# TagConnectProgrammer.net
KiCad netlist of a schematic drawn in Altium Designer
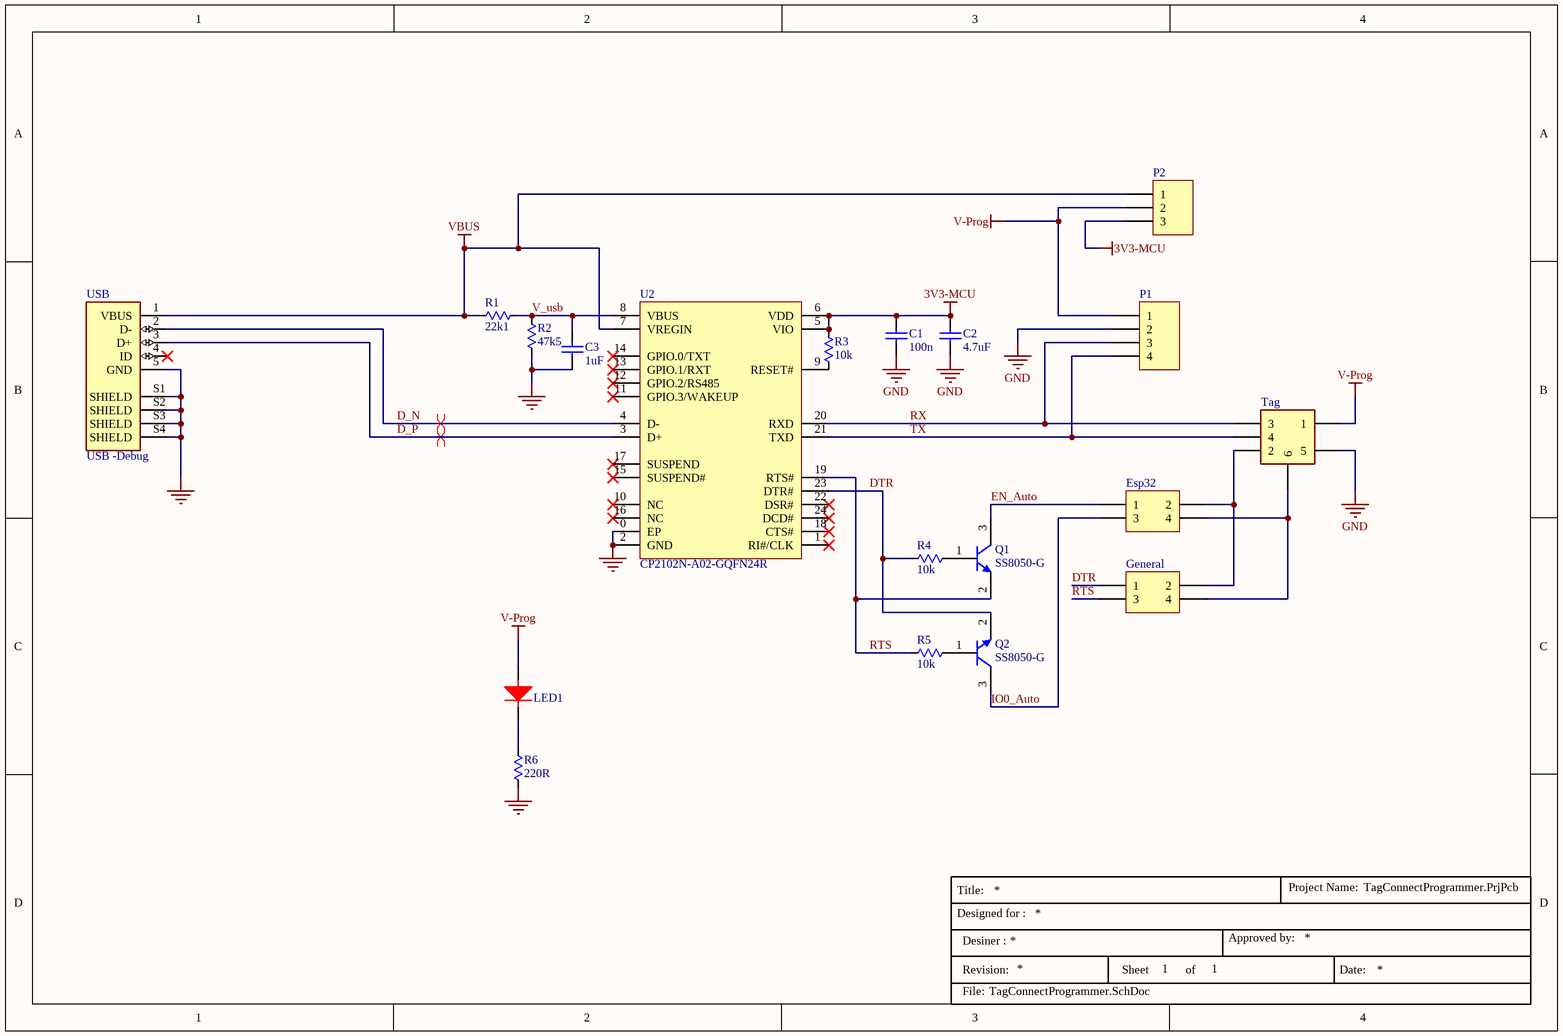
[diagram p0: TagConnectProgrammer.SchDoc]

(export (version "E")
  (design (tool "Eeschema 10.0.6"))
  (components
    (comp (ref "C1")
      (value "100n")
      (footprint "0603C")
      (description "Multilayer Ceramic Capacitors MLCC - SMD/SMT 16V 0.1uF X7R 0603 10%")
      (libsource (lib "Aves") (part "100n"))
    )
    (comp (ref "C2")
      (value "4.7uF")
      (footprint "0603C")
      (description "Multilayer Ceramic Capacitors MLCC - SMD/SMT 4.7uF+/-10% 10V X5R 1608")
      (libsource (lib "Aves") (part "4.7uF"))
    )
    (comp (ref "C3")
      (value "1uF")
      (footprint "0603C")
      (description "Multilayer Ceramic Capacitors MLCC - SMD/SMT 1uF+/-10% 10V X5R 1608")
      (libsource (lib "Aves") (part "1uF"))
    )
    (comp (ref "Esp32")
      (value "Header 2X2")
      (footprint "HDR2X2")
      (description "Header, 4-Pin, Dual row 100 mil")
      (fields (field (name "PUBLISHER") "Altium Limited"))
      (libsource (lib "Miscellaneous Connectors") (part "Header 2X2"))
    )
    (comp (ref "General")
      (value "Header 2X2")
      (footprint "HDR2X2")
      (description "Header, 4-Pin, Dual row 100 mil")
      (fields (field (name "PUBLISHER") "Altium Limited"))
      (libsource (lib "Miscellaneous Connectors") (part "Header 2X2"))
    )
    (comp (ref "LED1")
      (value "150060VS55040")
      (footprint "Würth_Elektronik_0_MFG")
      (description "Standard LEDs - SMD SMD 0603 RED")
      (libsource (lib "MikroFirm") (part "LED R"))
    )
    (comp (ref "P1")
      (value "Header 4")
      (footprint "HDR1X4")
      (description "Header, 4-Pin,One row 100 mil")
      (fields (field (name "PUBLISHER") "Altium Limited"))
      (libsource (lib "Miscellaneous Connectors") (part "Header 4"))
    )
    (comp (ref "P2")
      (value "Header 3")
      (footprint "HDR1X3")
      (description "Header, 3-Pin,One row 100 mil")
      (fields (field (name "PUBLISHER") "Altium Limited"))
      (libsource (lib "Miscellaneous Connectors") (part "Header 3"))
    )
    (comp (ref "Q1")
      (value "SS8050-G")
      (footprint "SOT95P240X115-3N")
      (description "NPN TRANSISTOR 1.5A 40V SOT-23 R")
      (libsource (lib "Aves") (part "SS8050-G"))
    )
    (comp (ref "Q2")
      (value "SS8050-G")
      (footprint "SOT95P240X115-3N")
      (description "NPN TRANSISTOR 1.5A 40V SOT-23 R")
      (libsource (lib "Aves") (part "SS8050-G"))
    )
    (comp (ref "R1")
      (value "22k1")
      (footprint "0603R")
      (description "Thick Film Resistors - SMD 0603 22Kohms 1% AEC-Q200")
      (libsource (lib "Aves") (part "22k1"))
    )
    (comp (ref "R2")
      (value "47k5")
      (footprint "0603R")
      (description "Thin Film Resistors - SMD 1/8W 47.5K ohm 1% 50ppm")
      (libsource (lib "Aves") (part "47k5"))
    )
    (comp (ref "R3")
      (value "10k")
      (footprint "0603R")
      (description "Thick Film Resistors - SMD 0603 10Kohms 1% AEC-Q200")
      (libsource (lib "Aves") (part "10k"))
    )
    (comp (ref "R4")
      (value "10k")
      (footprint "0603R")
      (description "Thick Film Resistors - SMD 0603 10Kohms 1% AEC-Q200")
      (libsource (lib "Aves") (part "10k"))
    )
    (comp (ref "R5")
      (value "10k")
      (footprint "0603R")
      (description "Thick Film Resistors - SMD 0603 10Kohms 1% AEC-Q200")
      (libsource (lib "Aves") (part "10k"))
    )
    (comp (ref "R6")
      (value "220R")
      (footprint "0603R")
      (description "Thick Film Resistors - SMD 220 Ohms 100-200 mW 0603 1%")
      (libsource (lib "MikroFirm") (part "220R"))
    )
    (comp (ref "Tag")
      (value "Header 3X2H BOX")
      (footprint "SHDRRA6W64P254X254_2X3_1528X885X910P")
      (description "Headers & Wire Housings WR-BHD 2.54mm Male 6P Angl Gold BoX Hdr")
      (fields
        (field (name "MANUFACTURER_PART_NUMBER") "61200621721")
        (field (name "MOUSER PART NUMBER") "710-61200621721")
      )
      (libsource (lib "MikroFirm") (part "Header 3X2H BOX"))
    )
    (comp (ref "U2")
      (value "CP2102N-A02-GQFN24R")
      (footprint "QFN50P400X400X80-25N")
      (description "IC USB TO UART BRIDGE QFN24")
      (libsource (lib "Aves") (part "CP2102N-A02-GQFN20R"))
    )
    (comp (ref "USB")
      (value "USB -Debug")
      (footprint "MOLEX_47642-0001")
      (description "USB - micro B Receptacle Connector 5 Position Board Edge, Cutout; Surface Mount, Right Angle")
      (libsource (lib "Aves") (part "USB - micro B"))
    )
  )
  (nets
    (net (code "1") (name "/DTR") (class "Default")
      (node (ref "General") (pin "1") (pinfunction "1_1") (pintype "passive"))
      (node (ref "Q2") (pin "2") (pinfunction "E_2") (pintype "passive"))
      (node (ref "R4") (pin "2") (pinfunction "2_2") (pintype "passive"))
      (node (ref "U2") (pin "23") (pinfunction "DTR#_23") (pintype "passive"))
    )
    (net (code "2") (name "/D_N") (class "Default")
      (node (ref "U2") (pin "4") (pinfunction "D-_4") (pintype "passive"))
      (node (ref "USB") (pin "2") (pinfunction "D-_2") (pintype "bidirectional"))
    )
    (net (code "3") (name "/D_P") (class "Default")
      (node (ref "U2") (pin "3") (pinfunction "D+_3") (pintype "passive"))
      (node (ref "USB") (pin "3") (pinfunction "D+_3") (pintype "bidirectional"))
    )
    (net (code "4") (name "/EN_Auto") (class "Default")
      (node (ref "Esp32") (pin "1") (pinfunction "1_1") (pintype "passive"))
      (node (ref "Q1") (pin "3") (pinfunction "C_3") (pintype "passive"))
    )
    (net (code "5") (name "/IO0_Auto") (class "Default")
      (node (ref "Esp32") (pin "3") (pinfunction "3_3") (pintype "passive"))
      (node (ref "Q2") (pin "3") (pinfunction "C_3") (pintype "passive"))
    )
    (net (code "6") (name "/RTS") (class "Default")
      (node (ref "General") (pin "3") (pinfunction "3_3") (pintype "passive"))
      (node (ref "Q1") (pin "2") (pinfunction "E_2") (pintype "passive"))
      (node (ref "R5") (pin "2") (pinfunction "2_2") (pintype "passive"))
      (node (ref "U2") (pin "19") (pinfunction "RTS#_19") (pintype "passive"))
    )
    (net (code "7") (name "/RX") (class "Default")
      (node (ref "P1") (pin "3") (pinfunction "3_3") (pintype "passive"))
      (node (ref "Tag") (pin "3") (pinfunction "3_3") (pintype "passive"))
      (node (ref "U2") (pin "20") (pinfunction "RXD_20") (pintype "passive"))
    )
    (net (code "8") (name "/TX") (class "Default")
      (node (ref "P1") (pin "4") (pinfunction "4_4") (pintype "passive"))
      (node (ref "Tag") (pin "4") (pinfunction "4_4") (pintype "passive"))
      (node (ref "U2") (pin "21") (pinfunction "TXD_21") (pintype "passive"))
    )
    (net (code "9") (name "/V_usb") (class "Default")
      (node (ref "C3") (pin "2") (pinfunction "2_2") (pintype "passive"))
      (node (ref "R1") (pin "2") (pinfunction "2_2") (pintype "passive"))
      (node (ref "R2") (pin "2") (pinfunction "2_2") (pintype "passive"))
      (node (ref "U2") (pin "8") (pinfunction "VBUS_8") (pintype "passive"))
    )
    (net (code "10") (name "3V3-MCU") (class "Default")
      (node (ref "C1") (pin "2") (pinfunction "2_2") (pintype "passive"))
      (node (ref "C2") (pin "2") (pinfunction "2_2") (pintype "passive"))
      (node (ref "P2") (pin "3") (pinfunction "3_3") (pintype "passive"))
      (node (ref "R3") (pin "2") (pinfunction "2_2") (pintype "passive"))
      (node (ref "U2") (pin "5") (pinfunction "VIO_5") (pintype "passive"))
      (node (ref "U2") (pin "6") (pinfunction "VDD_6") (pintype "passive"))
    )
    (net (code "11") (name "GND") (class "Default")
      (node (ref "C1") (pin "1") (pinfunction "1_1") (pintype "passive"))
      (node (ref "C2") (pin "1") (pinfunction "1_1") (pintype "passive"))
      (node (ref "C3") (pin "1") (pinfunction "1_1") (pintype "passive"))
      (node (ref "P1") (pin "2") (pinfunction "2_2") (pintype "passive"))
      (node (ref "R2") (pin "1") (pinfunction "1_1") (pintype "passive"))
      (node (ref "R6") (pin "1") (pinfunction "1_1") (pintype "passive"))
      (node (ref "Tag") (pin "5") (pinfunction "5_5") (pintype "passive"))
      (node (ref "U2") (pin "0") (pinfunction "EP_0") (pintype "passive"))
      (node (ref "U2") (pin "2") (pinfunction "GND_2") (pintype "passive"))
      (node (ref "USB") (pin "5") (pinfunction "GND_5") (pintype "power_in"))
      (node (ref "USB") (pin "S1") (pinfunction "SHIELD_S1") (pintype "power_in"))
      (node (ref "USB") (pin "S2") (pinfunction "SHIELD_S2") (pintype "power_in"))
      (node (ref "USB") (pin "S3") (pinfunction "SHIELD_S3") (pintype "power_in"))
      (node (ref "USB") (pin "S4") (pinfunction "SHIELD_S4") (pintype "power_in"))
    )
    (net (code "12") (name "Net-(Esp32-Pad2)") (class "Default")
      (node (ref "Esp32") (pin "2") (pinfunction "2_2") (pintype "passive"))
      (node (ref "General") (pin "2") (pinfunction "2_2") (pintype "passive"))
      (node (ref "Tag") (pin "2") (pinfunction "2_2") (pintype "passive"))
    )
    (net (code "13") (name "Net-(Esp32-Pad4)") (class "Default")
      (node (ref "Esp32") (pin "4") (pinfunction "4_4") (pintype "passive"))
      (node (ref "General") (pin "4") (pinfunction "4_4") (pintype "passive"))
      (node (ref "Tag") (pin "6") (pinfunction "6_6") (pintype "passive"))
    )
    (net (code "14") (name "Net-(LED1--)") (class "Default")
      (node (ref "LED1") (pin "1") (pinfunction "-_1") (pintype "passive"))
      (node (ref "R6") (pin "2") (pinfunction "2_2") (pintype "passive"))
    )
    (net (code "15") (name "Net-(Q1-B)") (class "Default")
      (node (ref "Q1") (pin "1") (pinfunction "B_1") (pintype "passive"))
      (node (ref "R4") (pin "1") (pinfunction "1_1") (pintype "passive"))
    )
    (net (code "16") (name "Net-(Q2-B)") (class "Default")
      (node (ref "Q2") (pin "1") (pinfunction "B_1") (pintype "passive"))
      (node (ref "R5") (pin "1") (pinfunction "1_1") (pintype "passive"))
    )
    (net (code "17") (name "Net-(U2-RESET#)") (class "Default")
      (node (ref "R3") (pin "1") (pinfunction "1_1") (pintype "passive"))
      (node (ref "U2") (pin "9") (pinfunction "RESET#_9") (pintype "passive"))
    )
    (net (code "18") (name "V-Prog") (class "Default")
      (node (ref "LED1") (pin "2") (pinfunction "+_2") (pintype "passive"))
      (node (ref "P1") (pin "1") (pinfunction "1_1") (pintype "passive"))
      (node (ref "P2") (pin "2") (pinfunction "2_2") (pintype "passive"))
      (node (ref "Tag") (pin "1") (pinfunction "1_1") (pintype "passive"))
    )
    (net (code "19") (name "VBUS") (class "Default")
      (node (ref "P2") (pin "1") (pinfunction "1_1") (pintype "passive"))
      (node (ref "R1") (pin "1") (pinfunction "1_1") (pintype "passive"))
      (node (ref "U2") (pin "7") (pinfunction "VREGIN_7") (pintype "passive"))
      (node (ref "USB") (pin "1") (pinfunction "VBUS_1") (pintype "power_in"))
    )
    (net (code "20") (name "unconnected-(U2-CTS#-Pad18)") (class "Default")
      (node (ref "U2") (pin "18") (pinfunction "CTS#_18") (pintype "passive+no_connect"))
    )
    (net (code "21") (name "unconnected-(U2-DCD#-Pad24)") (class "Default")
      (node (ref "U2") (pin "24") (pinfunction "DCD#_24") (pintype "passive+no_connect"))
    )
    (net (code "22") (name "unconnected-(U2-DSR#-Pad22)") (class "Default")
      (node (ref "U2") (pin "22") (pinfunction "DSR#_22") (pintype "passive+no_connect"))
    )
    (net (code "23") (name "unconnected-(U2-GPIO.0{slash}TXT-Pad14)") (class "Default")
      (node (ref "U2") (pin "14") (pinfunction "GPIO.0/TXT_14") (pintype "passive+no_connect"))
    )
    (net (code "24") (name "unconnected-(U2-GPIO.1{slash}RXT-Pad13)") (class "Default")
      (node (ref "U2") (pin "13") (pinfunction "GPIO.1/RXT_13") (pintype "passive+no_connect"))
    )
    (net (code "25") (name "unconnected-(U2-GPIO.2{slash}RS485-Pad12)") (class "Default")
      (node (ref "U2") (pin "12") (pinfunction "GPIO.2/RS485_12") (pintype "passive+no_connect"))
    )
    (net (code "26") (name "unconnected-(U2-GPIO.3{slash}WAKEUP-Pad11)") (class "Default")
      (node (ref "U2") (pin "11") (pinfunction "GPIO.3/WAKEUP_11") (pintype "passive+no_connect"))
    )
    (net (code "27") (name "unconnected-(U2-NC-Pad10)") (class "Default")
      (node (ref "U2") (pin "10") (pinfunction "NC_10") (pintype "passive+no_connect"))
    )
    (net (code "28") (name "unconnected-(U2-NC-Pad16)") (class "Default")
      (node (ref "U2") (pin "16") (pinfunction "NC_16") (pintype "passive+no_connect"))
    )
    (net (code "29") (name "unconnected-(U2-RI#{slash}CLK-Pad1)") (class "Default")
      (node (ref "U2") (pin "1") (pinfunction "RI#/CLK_1") (pintype "passive+no_connect"))
    )
    (net (code "30") (name "unconnected-(U2-SUSPEND#-Pad15)") (class "Default")
      (node (ref "U2") (pin "15") (pinfunction "SUSPEND#_15") (pintype "passive+no_connect"))
    )
    (net (code "31") (name "unconnected-(U2-SUSPEND-Pad17)") (class "Default")
      (node (ref "U2") (pin "17") (pinfunction "SUSPEND_17") (pintype "passive+no_connect"))
    )
    (net (code "32") (name "unconnected-(USB-ID-Pad4)") (class "Default")
      (node (ref "USB") (pin "4") (pinfunction "ID_4") (pintype "bidirectional+no_connect"))
    )
  )
)
